# Eagle.net
KiCad netlist of a schematic drawn in EAGLE
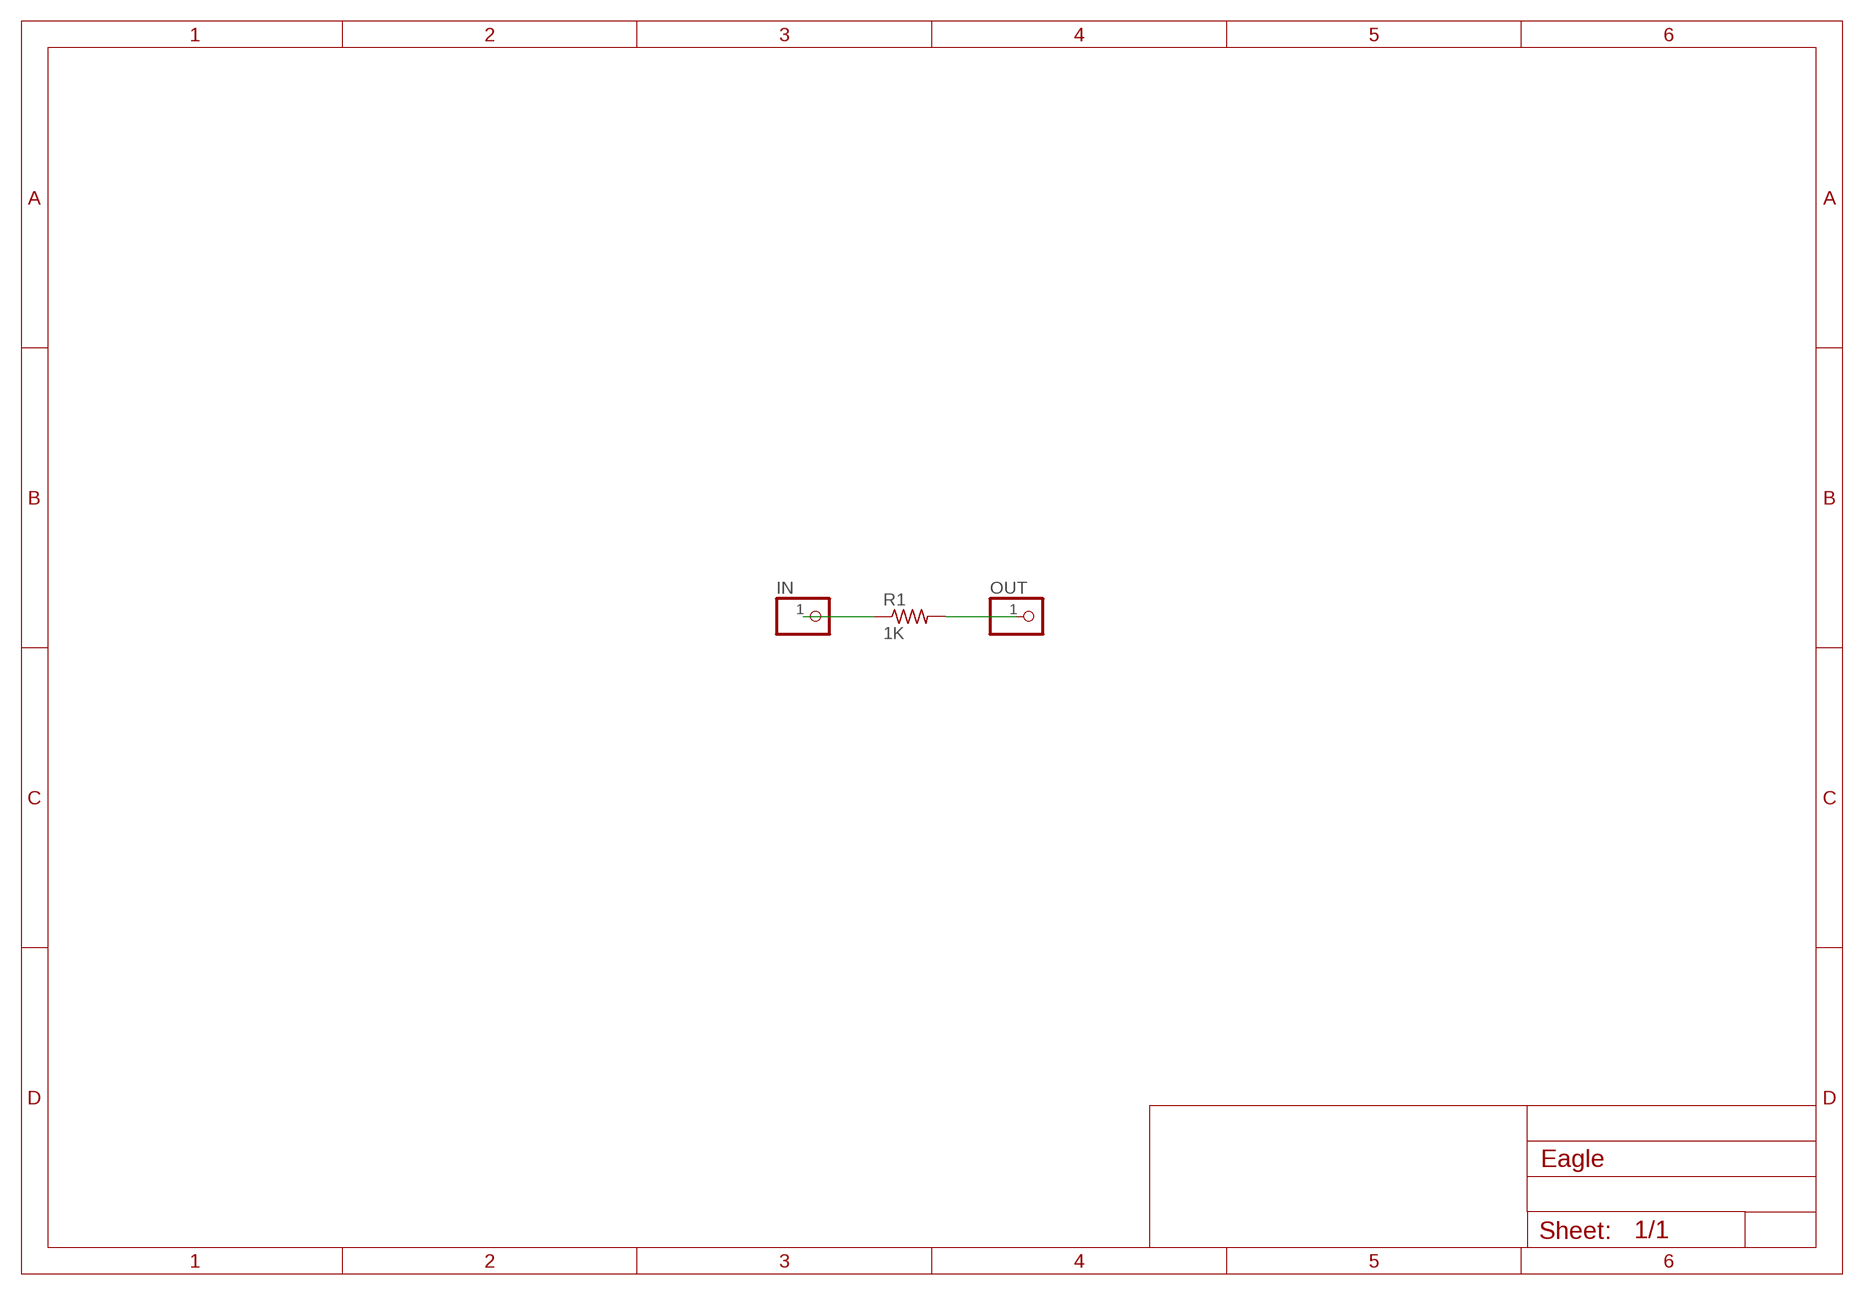
[diagram p0: schematic, sheet 1]

(export (version "E")
  (design (tool "Eeschema 10.0.6"))
  (components
    (comp (ref "IN")
      (value "PINHD-1X1")
      (footprint "eagle-import:1X01")
      (libsource (lib "eagle-import") (part "PINHD-1X1"))
    )
    (comp (ref "OUT")
      (value "PINHD-1X1")
      (footprint "eagle-import:1X01")
      (libsource (lib "eagle-import") (part "PINHD-1X1"))
    )
    (comp (ref "R1")
      (value "1K")
      (footprint "eagle-import:R0805")
      (libsource (lib "eagle-import") (part "R-US_R0805"))
    )
  )
  (nets
    (net (code "1") (name "Net-(IN-Pad1)") (class "Default")
      (node (ref "IN") (pin "1") (pinfunction "1_1") (pintype "passive"))
      (node (ref "R1") (pin "1") (pinfunction "1_1") (pintype "passive"))
    )
    (net (code "2") (name "Net-(OUT-Pad1)") (class "Default")
      (node (ref "OUT") (pin "1") (pinfunction "1_1") (pintype "passive"))
      (node (ref "R1") (pin "2") (pinfunction "2_2") (pintype "passive"))
    )
  )
)
